# WIRELESS.net
KiCad netlist of a schematic drawn in Altium Designer
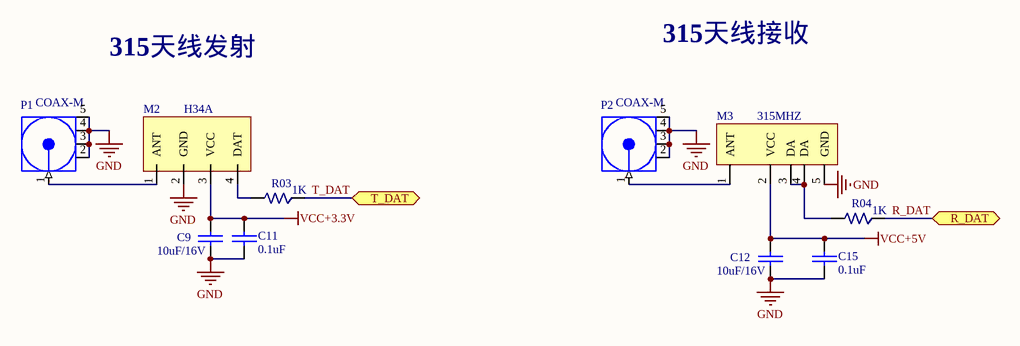
[diagram p0: WIRELESS.SchDoc]

(export (version "E")
  (design (tool "Eeschema 10.0.6"))
  (components
    (comp (ref "C9") (value "10uF/16V") (footprint "0805") (libsource (lib "INSPUR_SCH") (part "CAP")))
    (comp (ref "C11") (value "0.1uF") (footprint "0603") (libsource (lib "INSPUR_SCH") (part "CAP")))
    (comp (ref "C12") (value "10uF/16V") (footprint "0805") (libsource (lib "INSPUR_SCH") (part "CAP")))
    (comp (ref "C15") (value "0.1uF") (footprint "0603") (libsource (lib "INSPUR_SCH") (part "CAP")))
    (comp (ref "M2") (value "H34A") (footprint "H34A") (libsource (lib "INSPUR_PCB") (part "H34A")))
    (comp (ref "M3") (value "315MHZ") (footprint "315MHZ") (libsource (lib "INSPUR_PCB") (part "315MHZ")))
    (comp (ref "P1")
      (value "COAX-M")
      (footprint "ST-TH1")
      (description "SMA-J-P-H-ST-TH1")
      (fields (field (name "PUBLISHER") "Altium Limited"))
      (libsource (lib "Miscellaneous Connectors") (part "COAX-M"))
    )
    (comp (ref "P2")
      (value "COAX-M")
      (footprint "ST-TH1")
      (description "SMA-J-P-H-ST-TH1")
      (fields (field (name "PUBLISHER") "Altium Limited"))
      (libsource (lib "Miscellaneous Connectors") (part "COAX-M"))
    )
    (comp (ref "R03")
      (value "1K")
      (footprint "0603")
      (description "高精度电阻")
      (libsource (lib "8CF_V6") (part "RES-1%"))
    )
    (comp (ref "R04")
      (value "1K")
      (footprint "0603")
      (description "高精度电阻")
      (libsource (lib "8CF_V6") (part "RES-1%"))
    )
  )
  (nets
    (net (code "1") (name "/R_DAT") (class "Default") (node (ref "R04") (pin "1") (pintype "passive")))
    (net (code "2") (name "/T_DAT") (class "Default") (node (ref "R03") (pin "1") (pintype "passive")))
    (net (code "3") (name "GND") (class "Default")
      (node (ref "C11") (pin "2") (pinfunction "2_2") (pintype "passive"))
      (node (ref "C12") (pin "2") (pinfunction "2_2") (pintype "passive"))
      (node (ref "C15") (pin "2") (pinfunction "2_2") (pintype "passive"))
      (node (ref "C9") (pin "1") (pinfunction "1_1") (pintype "passive"))
      (node (ref "M2") (pin "2") (pinfunction "GND_2") (pintype "passive"))
      (node (ref "M3") (pin "5") (pinfunction "GND_5") (pintype "passive"))
      (node (ref "P1") (pin "2") (pinfunction "GND_2") (pintype "power_in"))
      (node (ref "P1") (pin "3") (pinfunction "GND_3") (pintype "power_in"))
      (node (ref "P1") (pin "4") (pinfunction "GND_4") (pintype "power_in"))
      (node (ref "P1") (pin "5") (pinfunction "GND_5") (pintype "power_in"))
      (node (ref "P2") (pin "2") (pinfunction "GND_2") (pintype "power_in"))
      (node (ref "P2") (pin "3") (pinfunction "GND_3") (pintype "power_in"))
      (node (ref "P2") (pin "4") (pinfunction "GND_4") (pintype "power_in"))
      (node (ref "P2") (pin "5") (pinfunction "GND_5") (pintype "power_in"))
    )
    (net (code "4") (name "Net-(M2-ANT)") (class "Default")
      (node (ref "M2") (pin "1") (pinfunction "ANT_1") (pintype "passive"))
      (node (ref "P1") (pin "1") (pinfunction "Signal_1") (pintype "input"))
    )
    (net (code "5") (name "Net-(M2-DAT)") (class "Default")
      (node (ref "M2") (pin "4") (pinfunction "DAT_4") (pintype "passive"))
      (node (ref "R03") (pin "2") (pintype "passive"))
    )
    (net (code "6") (name "Net-(M3-ANT)") (class "Default")
      (node (ref "M3") (pin "1") (pinfunction "ANT_1") (pintype "passive"))
      (node (ref "P2") (pin "1") (pinfunction "Signal_1") (pintype "input"))
    )
    (net (code "7") (name "Net-(M3-DA-Pad3)") (class "Default")
      (node (ref "M3") (pin "3") (pinfunction "DA_3") (pintype "passive"))
      (node (ref "M3") (pin "4") (pinfunction "DA_4") (pintype "passive"))
      (node (ref "R04") (pin "2") (pintype "passive"))
    )
    (net (code "8") (name "VCC+3.3V") (class "Default")
      (node (ref "C11") (pin "1") (pinfunction "1_1") (pintype "passive"))
      (node (ref "C9") (pin "2") (pinfunction "2_2") (pintype "passive"))
      (node (ref "M2") (pin "3") (pinfunction "VCC_3") (pintype "passive"))
    )
    (net (code "9") (name "VCC+5V") (class "Default")
      (node (ref "C12") (pin "1") (pinfunction "1_1") (pintype "passive"))
      (node (ref "C15") (pin "1") (pinfunction "1_1") (pintype "passive"))
      (node (ref "M3") (pin "2") (pinfunction "VCC_2") (pintype "passive"))
    )
  )
)
